# MS6205-Arduino.net
KiCad netlist of a schematic drawn in EAGLE
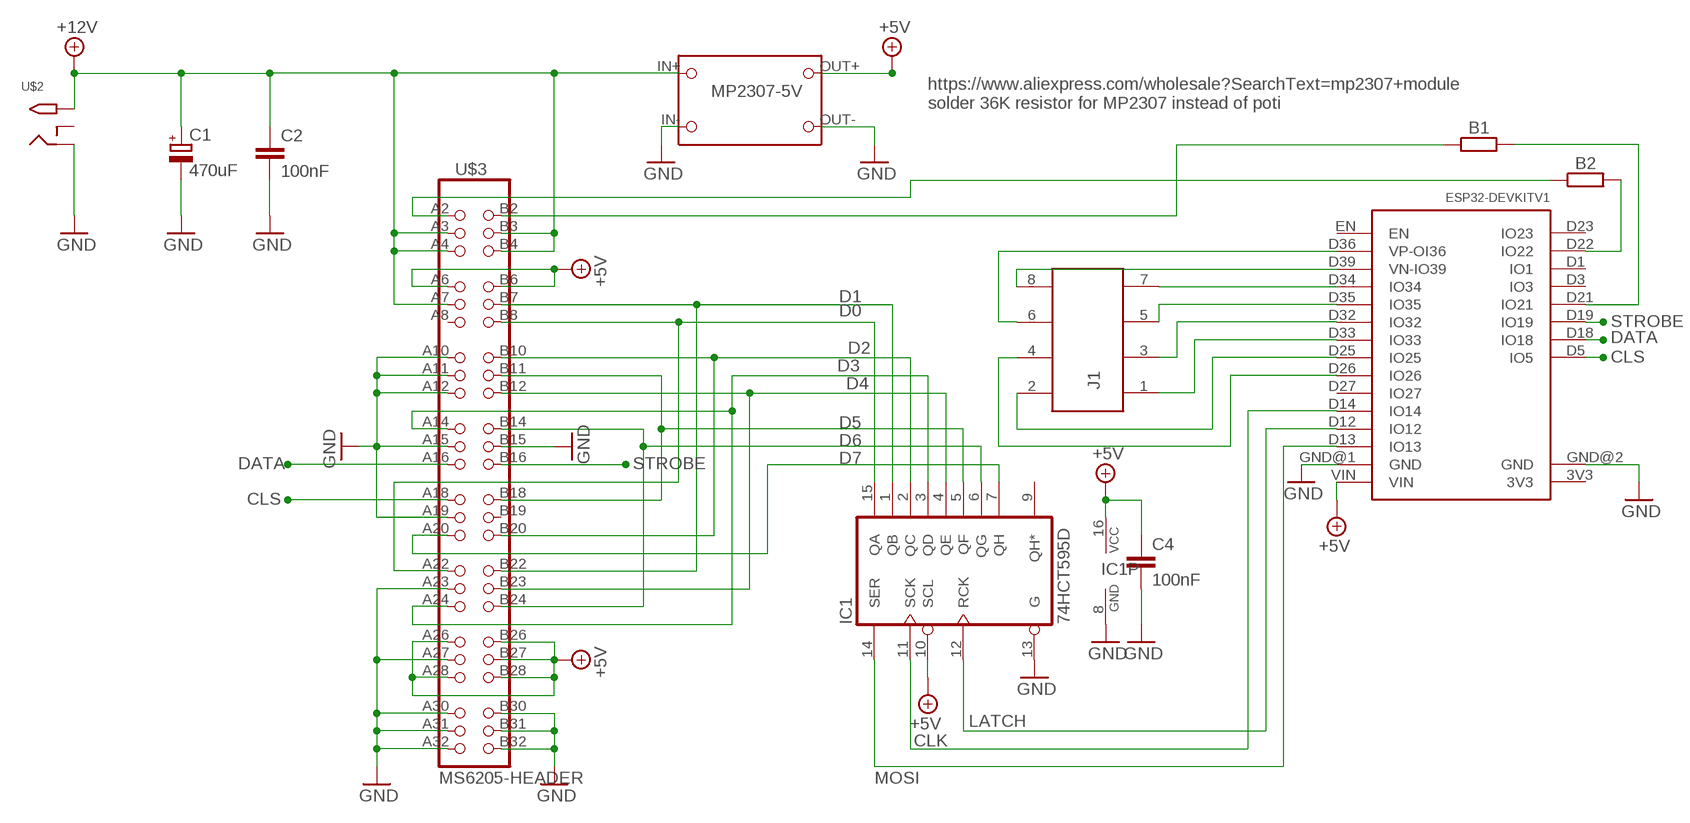
[diagram p0: schematic, sheet 1]

(export (version "E")
  (design (tool "Eeschema 10.0.6"))
  (components
    (comp (ref "B1")
      (value "0")
      (footprint "eagle-import:0204_5")
      (libsource (lib "eagle-import") (part "R-EU_0204/5"))
    )
    (comp (ref "B2")
      (value "0")
      (footprint "eagle-import:0204_5")
      (libsource (lib "eagle-import") (part "R-EU_0204/5"))
    )
    (comp (ref "C1")
      (value "470uF")
      (footprint "eagle-import:150CLZ-1010")
      (libsource (lib "eagle-import") (part "CPOL-EU150CLZ-1010"))
    )
    (comp (ref "C2")
      (value "100nF")
      (footprint "eagle-import:C1206")
      (libsource (lib "eagle-import") (part "C-EUC1206"))
    )
    (comp (ref "C4")
      (value "100nF")
      (footprint "eagle-import:C0805")
      (libsource (lib "eagle-import") (part "C-EUC0805"))
    )
    (comp (ref "IC1")
      (value "74HCT595D")
      (footprint "eagle-import:SO16")
      (libsource (lib "eagle-import") (part "74595DHCT"))
    )
    (comp (ref "J1")
      (value "61200822323")
      (footprint "eagle-import:61200822323")
      (libsource (lib "eagle-import") (part "61200822323"))
    )
    (comp (ref "MP2307-5V")
      (value "PWS-MP2307")
      (footprint "eagle-import:MP2307-PWS")
      (libsource (lib "eagle-import") (part "PWS-MP2307"))
    )
    (comp (ref "U$1")
      (value "ESP32DEVKIT1-REDUCED")
      (footprint "eagle-import:ESP32-DEVKIT1-REDUCED")
      (fields (field (name "SPICEPREFIX") "X"))
      (libsource (lib "eagle-import") (part "ESP32DEVKIT1-REDUCED"))
    )
    (comp (ref "U$2")
      (value "2.1MMJACKTHM")
      (footprint "eagle-import:PJ-102A")
      (libsource (lib "eagle-import") (part "2.1MMJACKTHM"))
    )
    (comp (ref "U$3")
      (value "MS6205-HEADER")
      (footprint "eagle-import:MS6205_CONNECTOR_HOLE")
      (libsource (lib "eagle-import") (part "MS6205-HEADER"))
    )
  )
  (nets
    (net (code "1") (name "+5V") (class "Default")
      (node (ref "C4") (pin "1") (pinfunction "1_1") (pintype "passive"))
      (node (ref "IC1") (pin "10") (pinfunction "SCL_10") (pintype "input"))
      (node (ref "IC1") (pin "16") (pinfunction "VCC_16") (pintype "power_in"))
      (node (ref "MP2307-5V") (pin "OUT+") (pinfunction "OUT+_OUT+") (pintype "output"))
      (node (ref "U$1") (pin "VIN") (pinfunction "VIN_VIN") (pintype "bidirectional"))
      (node (ref "U$3") (pin "A26") (pinfunction "A26_A26") (pintype "passive"))
      (node (ref "U$3") (pin "A28") (pinfunction "A28_A28") (pintype "passive"))
      (node (ref "U$3") (pin "A6") (pinfunction "A6_A6") (pintype "passive"))
      (node (ref "U$3") (pin "B26") (pinfunction "B26_B26") (pintype "passive"))
      (node (ref "U$3") (pin "B27") (pinfunction "B27_B27") (pintype "passive"))
      (node (ref "U$3") (pin "B28") (pinfunction "B28_B28") (pintype "passive"))
      (node (ref "U$3") (pin "B6") (pinfunction "B6_B6") (pintype "passive"))
    )
    (net (code "2") (name "+12V") (class "Default")
      (node (ref "C1") (pin "+") (pinfunction "+_+") (pintype "passive"))
      (node (ref "C2") (pin "1") (pinfunction "1_1") (pintype "passive"))
      (node (ref "MP2307-5V") (pin "IN+") (pinfunction "IN+_IN+") (pintype "input"))
      (node (ref "U$2") (pin "TIP") (pinfunction "TIP_TIP") (pintype "bidirectional"))
      (node (ref "U$3") (pin "A3") (pinfunction "A3_A3") (pintype "passive"))
      (node (ref "U$3") (pin "A4") (pinfunction "A4_A4") (pintype "passive"))
      (node (ref "U$3") (pin "A7") (pinfunction "A7_A7") (pintype "passive"))
      (node (ref "U$3") (pin "B3") (pinfunction "B3_B3") (pintype "passive"))
      (node (ref "U$3") (pin "B4") (pinfunction "B4_B4") (pintype "passive"))
    )
    (net (code "3") (name "/CLK") (class "Default")
      (node (ref "IC1") (pin "11") (pinfunction "SCK_11") (pintype "input"))
      (node (ref "U$1") (pin "D14") (pinfunction "IO14_D14") (pintype "bidirectional"))
    )
    (net (code "4") (name "/CLS") (class "Default")
      (node (ref "U$1") (pin "D5") (pinfunction "IO5_D5") (pintype "bidirectional"))
      (node (ref "U$3") (pin "A18") (pinfunction "A18_A18") (pintype "passive"))
    )
    (net (code "5") (name "/D0") (class "Default")
      (node (ref "IC1") (pin "15") (pinfunction "QA_15") (pintype "tri_state"))
      (node (ref "U$3") (pin "A22") (pinfunction "A22_A22") (pintype "passive"))
      (node (ref "U$3") (pin "B8") (pinfunction "B8_B8") (pintype "passive"))
    )
    (net (code "6") (name "/D1") (class "Default")
      (node (ref "IC1") (pin "1") (pinfunction "QB_1") (pintype "tri_state"))
      (node (ref "U$3") (pin "B22") (pinfunction "B22_B22") (pintype "passive"))
      (node (ref "U$3") (pin "B7") (pinfunction "B7_B7") (pintype "passive"))
    )
    (net (code "7") (name "/D2") (class "Default")
      (node (ref "IC1") (pin "2") (pinfunction "QC_2") (pintype "tri_state"))
      (node (ref "U$3") (pin "B10") (pinfunction "B10_B10") (pintype "passive"))
      (node (ref "U$3") (pin "B20") (pinfunction "B20_B20") (pintype "passive"))
    )
    (net (code "8") (name "/D3") (class "Default")
      (node (ref "IC1") (pin "3") (pinfunction "QD_3") (pintype "tri_state"))
      (node (ref "U$3") (pin "A14") (pinfunction "A14_A14") (pintype "passive"))
      (node (ref "U$3") (pin "A24") (pinfunction "A24_A24") (pintype "passive"))
    )
    (net (code "9") (name "/D4") (class "Default")
      (node (ref "IC1") (pin "4") (pinfunction "QE_4") (pintype "tri_state"))
      (node (ref "U$3") (pin "B12") (pinfunction "B12_B12") (pintype "passive"))
      (node (ref "U$3") (pin "B23") (pinfunction "B23_B23") (pintype "passive"))
    )
    (net (code "10") (name "/D5") (class "Default")
      (node (ref "IC1") (pin "5") (pinfunction "QF_5") (pintype "tri_state"))
      (node (ref "U$3") (pin "B11") (pinfunction "B11_B11") (pintype "passive"))
      (node (ref "U$3") (pin "B18") (pinfunction "B18_B18") (pintype "passive"))
    )
    (net (code "11") (name "/D6") (class "Default")
      (node (ref "IC1") (pin "6") (pinfunction "QG_6") (pintype "tri_state"))
      (node (ref "U$3") (pin "B14") (pinfunction "B14_B14") (pintype "passive"))
      (node (ref "U$3") (pin "B24") (pinfunction "B24_B24") (pintype "passive"))
    )
    (net (code "12") (name "/D7") (class "Default")
      (node (ref "IC1") (pin "7") (pinfunction "QH_7") (pintype "tri_state"))
      (node (ref "U$3") (pin "A20") (pinfunction "A20_A20") (pintype "passive"))
    )
    (net (code "13") (name "/DATA") (class "Default")
      (node (ref "U$1") (pin "D18") (pinfunction "IO18_D18") (pintype "bidirectional"))
      (node (ref "U$3") (pin "A16") (pinfunction "A16_A16") (pintype "passive"))
    )
    (net (code "14") (name "/LATCH") (class "Default")
      (node (ref "IC1") (pin "12") (pinfunction "RCK_12") (pintype "input"))
      (node (ref "U$1") (pin "D12") (pinfunction "IO12_D12") (pintype "bidirectional"))
    )
    (net (code "15") (name "/MOSI") (class "Default")
      (node (ref "IC1") (pin "14") (pinfunction "SER_14") (pintype "input"))
      (node (ref "U$1") (pin "D13") (pinfunction "IO13_D13") (pintype "bidirectional"))
    )
    (net (code "16") (name "/STROBE") (class "Default")
      (node (ref "U$1") (pin "D19") (pinfunction "IO19_D19") (pintype "bidirectional"))
      (node (ref "U$3") (pin "B16") (pinfunction "B16_B16") (pintype "passive"))
    )
    (net (code "17") (name "GND") (class "Default")
      (node (ref "C1") (pin "-") (pinfunction "-_-") (pintype "passive"))
      (node (ref "C2") (pin "2") (pinfunction "2_2") (pintype "passive"))
      (node (ref "C4") (pin "2") (pinfunction "2_2") (pintype "passive"))
      (node (ref "IC1") (pin "13") (pinfunction "G_13") (pintype "input"))
      (node (ref "IC1") (pin "8") (pinfunction "GND_8") (pintype "power_in"))
      (node (ref "MP2307-5V") (pin "IN-") (pinfunction "IN-_IN-") (pintype "input"))
      (node (ref "MP2307-5V") (pin "OUT-") (pinfunction "OUT-_OUT-") (pintype "output"))
      (node (ref "U$1") (pin "GND@1") (pinfunction "GND_GND@1") (pintype "bidirectional"))
      (node (ref "U$1") (pin "GND@2") (pinfunction "GND_GND@2") (pintype "bidirectional"))
      (node (ref "U$2") (pin "RING") (pinfunction "RING_RING") (pintype "bidirectional"))
      (node (ref "U$3") (pin "A10") (pinfunction "A10_A10") (pintype "passive"))
      (node (ref "U$3") (pin "A11") (pinfunction "A11_A11") (pintype "passive"))
      (node (ref "U$3") (pin "A12") (pinfunction "A12_A12") (pintype "passive"))
      (node (ref "U$3") (pin "A15") (pinfunction "A15_A15") (pintype "passive"))
      (node (ref "U$3") (pin "A19") (pinfunction "A19_A19") (pintype "passive"))
      (node (ref "U$3") (pin "A23") (pinfunction "A23_A23") (pintype "passive"))
      (node (ref "U$3") (pin "A27") (pinfunction "A27_A27") (pintype "passive"))
      (node (ref "U$3") (pin "A30") (pinfunction "A30_A30") (pintype "passive"))
      (node (ref "U$3") (pin "A31") (pinfunction "A31_A31") (pintype "passive"))
      (node (ref "U$3") (pin "A32") (pinfunction "A32_A32") (pintype "passive"))
      (node (ref "U$3") (pin "B15") (pinfunction "B15_B15") (pintype "passive"))
      (node (ref "U$3") (pin "B30") (pinfunction "B30_B30") (pintype "passive"))
      (node (ref "U$3") (pin "B31") (pinfunction "B31_B31") (pintype "passive"))
      (node (ref "U$3") (pin "B32") (pinfunction "B32_B32") (pintype "passive"))
    )
    (net (code "18") (name "Net-(B1-Pad1)") (class "Default")
      (node (ref "B1") (pin "1") (pinfunction "1_1") (pintype "passive"))
      (node (ref "U$3") (pin "B2") (pinfunction "B2_B2") (pintype "passive"))
    )
    (net (code "19") (name "Net-(B2-Pad1)") (class "Default")
      (node (ref "B2") (pin "1") (pinfunction "1_1") (pintype "passive"))
      (node (ref "U$3") (pin "A2") (pinfunction "A2_A2") (pintype "passive"))
    )
    (net (code "20") (name "Net-(U$1-IO21)") (class "Default")
      (node (ref "B1") (pin "2") (pinfunction "2_2") (pintype "passive"))
      (node (ref "U$1") (pin "D21") (pinfunction "IO21_D21") (pintype "bidirectional"))
    )
    (net (code "21") (name "Net-(U$1-IO22)") (class "Default")
      (node (ref "B2") (pin "2") (pinfunction "2_2") (pintype "passive"))
      (node (ref "U$1") (pin "D22") (pinfunction "IO22_D22") (pintype "bidirectional"))
    )
    (net (code "22") (name "Net-(U$1-IO25)") (class "Default")
      (node (ref "J1") (pin "2") (pinfunction "2_2") (pintype "passive"))
      (node (ref "U$1") (pin "D25") (pinfunction "IO25_D25") (pintype "bidirectional"))
    )
    (net (code "23") (name "Net-(U$1-IO26)") (class "Default")
      (node (ref "J1") (pin "4") (pinfunction "4_4") (pintype "passive"))
      (node (ref "U$1") (pin "D26") (pinfunction "IO26_D26") (pintype "bidirectional"))
    )
    (net (code "24") (name "Net-(U$1-IO32)") (class "Default")
      (node (ref "J1") (pin "3") (pinfunction "3_3") (pintype "passive"))
      (node (ref "U$1") (pin "D32") (pinfunction "IO32_D32") (pintype "bidirectional"))
    )
    (net (code "25") (name "Net-(U$1-IO33)") (class "Default")
      (node (ref "J1") (pin "1") (pinfunction "1_1") (pintype "passive"))
      (node (ref "U$1") (pin "D33") (pinfunction "IO33_D33") (pintype "bidirectional"))
    )
    (net (code "26") (name "Net-(U$1-IO34)") (class "Default")
      (node (ref "J1") (pin "7") (pinfunction "7_7") (pintype "passive"))
      (node (ref "U$1") (pin "D34") (pinfunction "IO34_D34") (pintype "bidirectional"))
    )
    (net (code "27") (name "Net-(U$1-IO35)") (class "Default")
      (node (ref "J1") (pin "5") (pinfunction "5_5") (pintype "passive"))
      (node (ref "U$1") (pin "D35") (pinfunction "IO35_D35") (pintype "bidirectional"))
    )
    (net (code "28") (name "Net-(U$1-VN-IO39)") (class "Default")
      (node (ref "J1") (pin "8") (pinfunction "8_8") (pintype "passive"))
      (node (ref "U$1") (pin "D39") (pinfunction "VN-IO39_D39") (pintype "bidirectional"))
    )
    (net (code "29") (name "Net-(U$1-VP-OI36)") (class "Default")
      (node (ref "J1") (pin "6") (pinfunction "6_6") (pintype "passive"))
      (node (ref "U$1") (pin "D36") (pinfunction "VP-OI36_D36") (pintype "bidirectional"))
    )
    (net (code "30") (name "unconnected-(IC1A-QH*-Pad9)") (class "Default")
      (node (ref "IC1") (pin "9") (pinfunction "QH*_9") (pintype "tri_state"))
    )
    (net (code "31") (name "unconnected-(U$1-IO1-PadD1)") (class "Default")
      (node (ref "U$1") (pin "D1") (pinfunction "IO1_D1") (pintype "bidirectional"))
    )
    (net (code "32") (name "unconnected-(U$1-IO3-PadD3)") (class "Default")
      (node (ref "U$1") (pin "D3") (pinfunction "IO3_D3") (pintype "bidirectional"))
    )
    (net (code "33") (name "unconnected-(U$1-IO23-PadD23)") (class "Default")
      (node (ref "U$1") (pin "D23") (pinfunction "IO23_D23") (pintype "bidirectional"))
    )
    (net (code "34") (name "unconnected-(U$1-IO27-PadD27)") (class "Default")
      (node (ref "U$1") (pin "D27") (pinfunction "IO27_D27") (pintype "bidirectional"))
    )
    (net (code "35") (name "unconnected-(U$1-Pad3V3)") (class "Default")
      (node (ref "U$1") (pin "3V3") (pinfunction "3V3_3V3") (pintype "bidirectional"))
    )
    (net (code "36") (name "unconnected-(U$1-PadEN)") (class "Default")
      (node (ref "U$1") (pin "EN") (pinfunction "EN_EN") (pintype "bidirectional"))
    )
    (net (code "37") (name "unconnected-(U$2-PadRING_SW)") (class "Default")
      (node (ref "U$2") (pin "RING_SW") (pinfunction "RING_SW_RING_SW") (pintype "bidirectional"))
    )
    (net (code "38") (name "unconnected-(U$3-PadA8)") (class "Default")
      (node (ref "U$3") (pin "A8") (pinfunction "A8_A8") (pintype "passive"))
    )
    (net (code "39") (name "unconnected-(U$3-PadB19)") (class "Default")
      (node (ref "U$3") (pin "B19") (pinfunction "B19_B19") (pintype "passive"))
    )
  )
)
